# 08_SAMA7G54-DDR3.net
KiCad netlist of a schematic drawn in Altium Designer
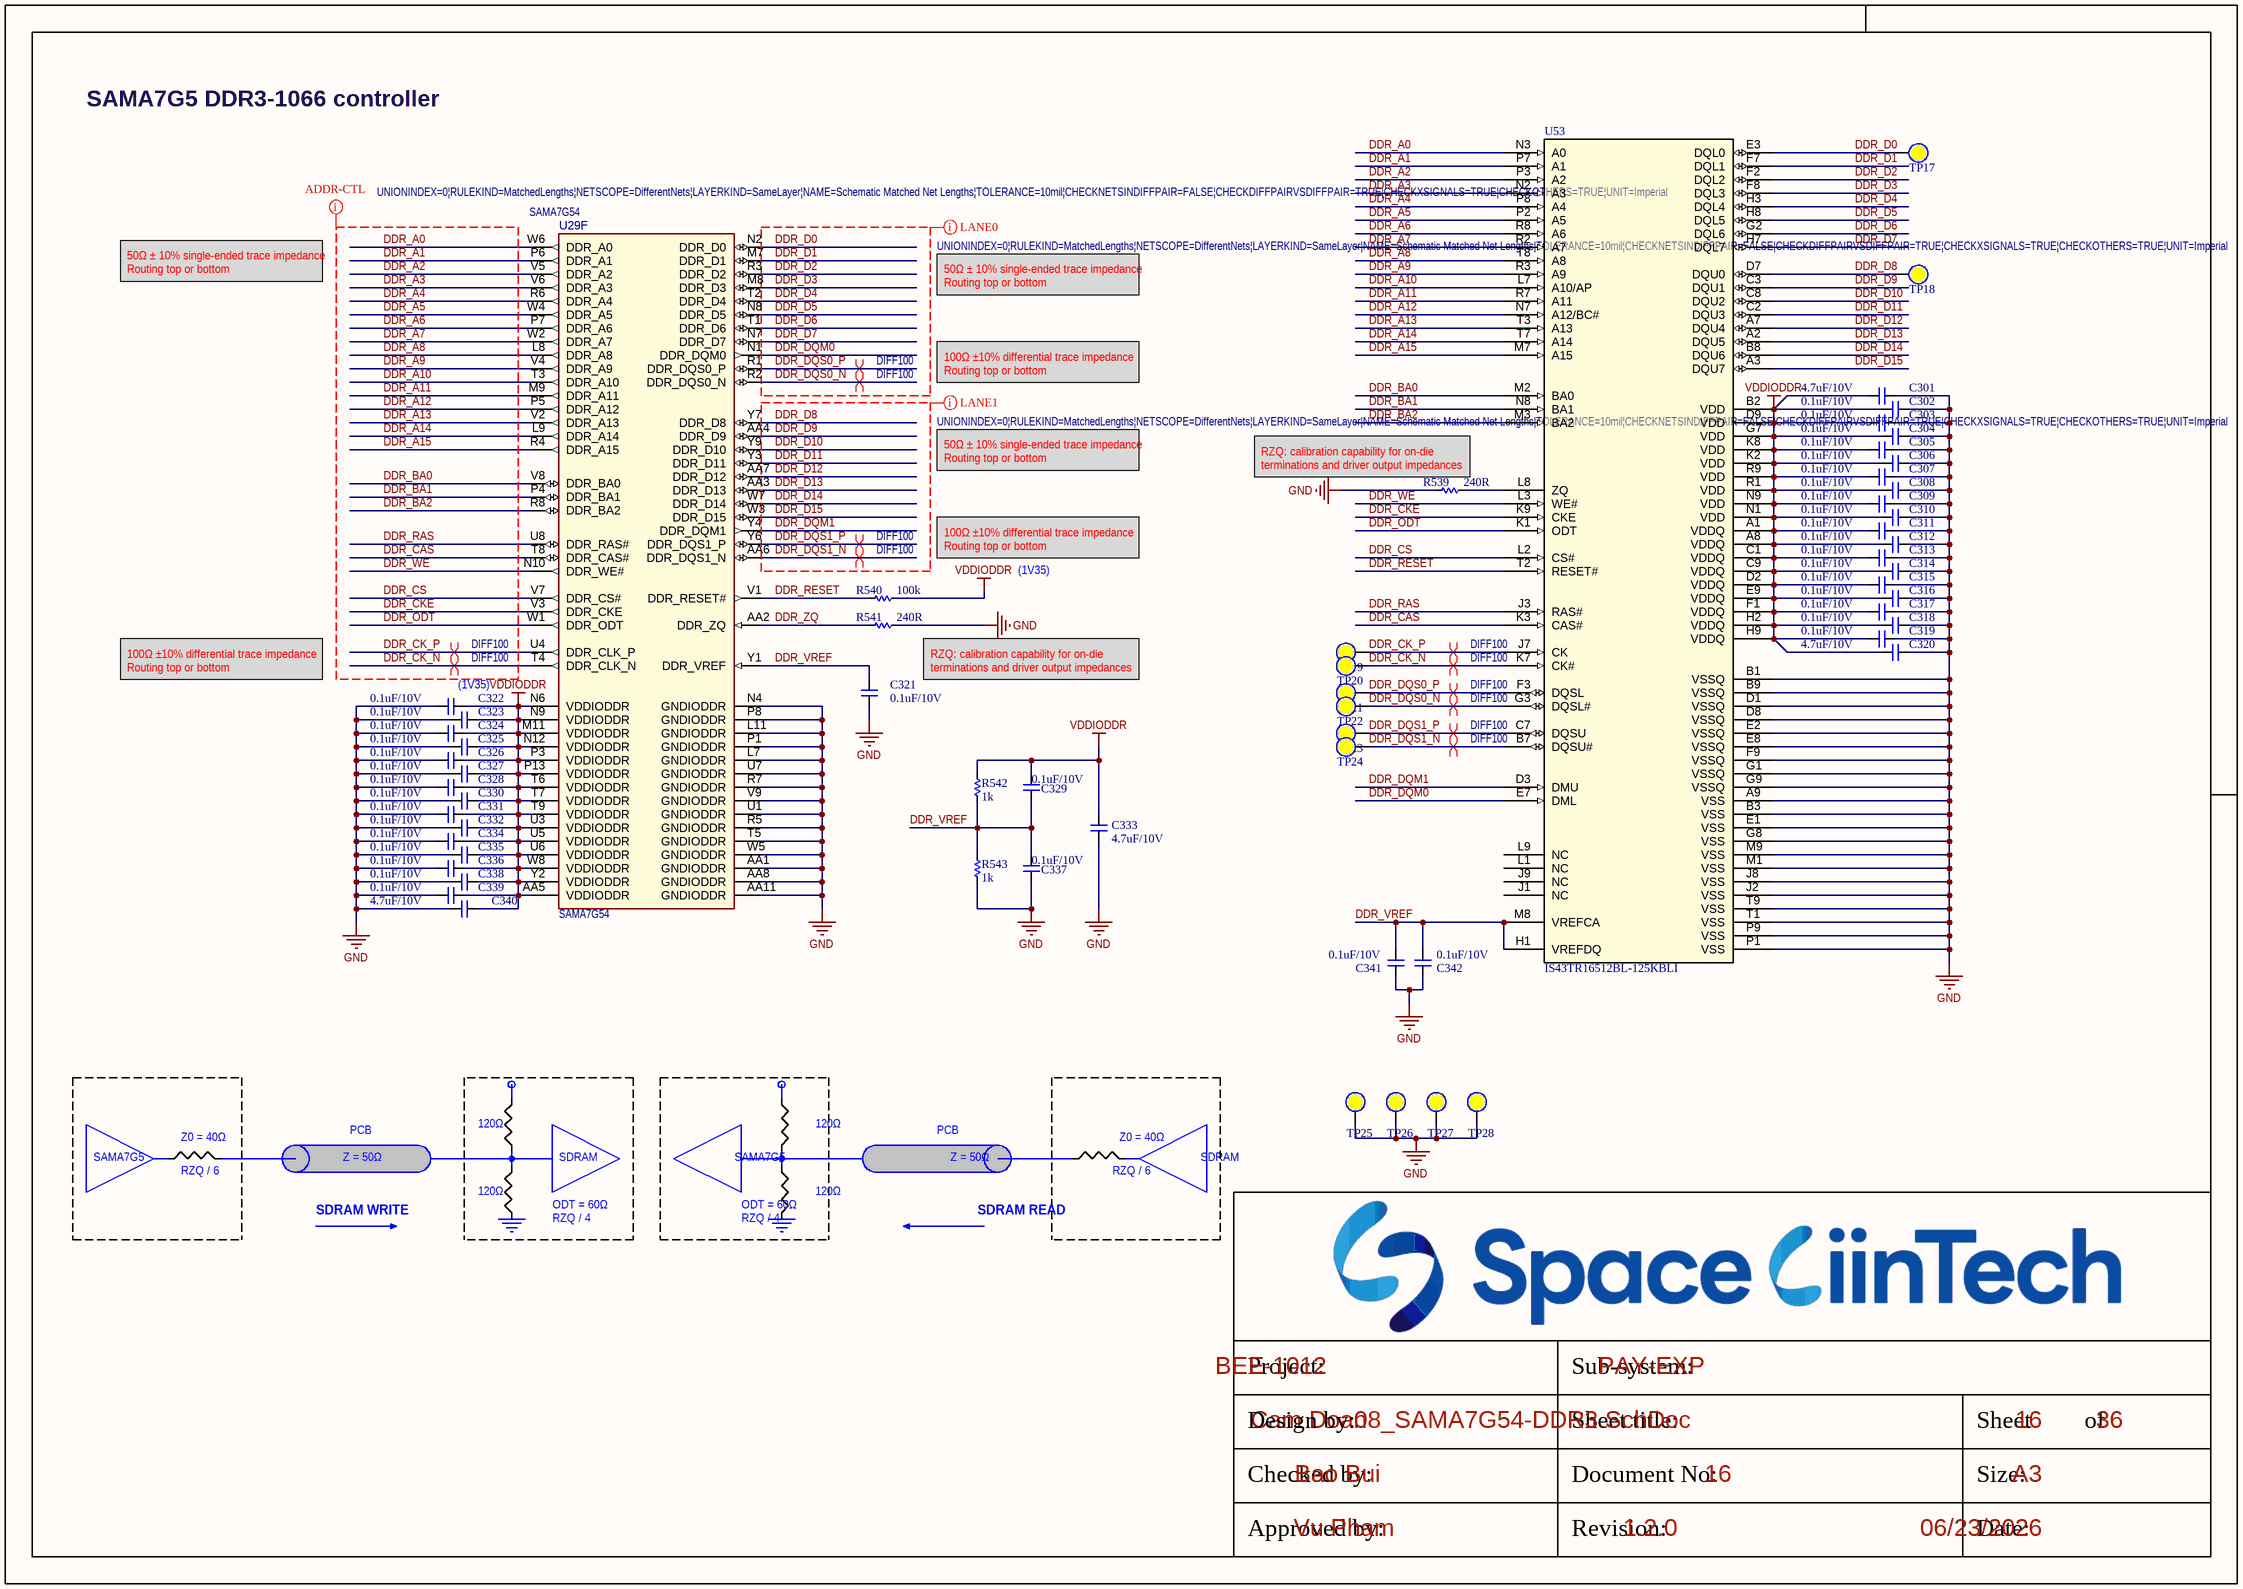
[diagram p0: 08_SAMA7G54-DDR3.SchDoc]

(export (version "E")
  (design (tool "Eeschema 10.0.6"))
  (components
    (comp (ref "C301")
      (value "4.7uF/10V")
      (footprint "CAP_C_1005X50_L")
      (description "CAP")
      (libsource (lib "LABLIB") (part "_CAP_C_2"))
    )
    (comp (ref "C302")
      (value "0.1uF/10V")
      (footprint "CAP_C_0603x30")
      (description "CAP")
      (libsource (lib "LABLIB") (part "_CAP_C_2"))
    )
    (comp (ref "C303")
      (value "0.1uF/10V")
      (footprint "CAP_C_0603x30")
      (description "CAP")
      (libsource (lib "LABLIB") (part "_CAP_C_2"))
    )
    (comp (ref "C304")
      (value "0.1uF/10V")
      (footprint "CAP_C_0603x30")
      (description "CAP")
      (libsource (lib "LABLIB") (part "_CAP_C_2"))
    )
    (comp (ref "C305")
      (value "0.1uF/10V")
      (footprint "CAP_C_0603x30")
      (description "CAP")
      (libsource (lib "LABLIB") (part "_CAP_C_2"))
    )
    (comp (ref "C306")
      (value "0.1uF/10V")
      (footprint "CAP_C_0603x30")
      (description "CAP")
      (libsource (lib "LABLIB") (part "_CAP_C_2"))
    )
    (comp (ref "C307")
      (value "0.1uF/10V")
      (footprint "CAP_C_0603x30")
      (description "CAP")
      (libsource (lib "LABLIB") (part "_CAP_C_2"))
    )
    (comp (ref "C308")
      (value "0.1uF/10V")
      (footprint "CAP_C_0603x30")
      (description "CAP")
      (libsource (lib "LABLIB") (part "_CAP_C_2"))
    )
    (comp (ref "C309")
      (value "0.1uF/10V")
      (footprint "CAP_C_0603x30")
      (description "CAP")
      (libsource (lib "LABLIB") (part "_CAP_C_2"))
    )
    (comp (ref "C310")
      (value "0.1uF/10V")
      (footprint "CAP_C_0603x30")
      (description "CAP")
      (libsource (lib "LABLIB") (part "_CAP_C_2"))
    )
    (comp (ref "C311")
      (value "0.1uF/10V")
      (footprint "CAP_C_0603x30")
      (description "CAP")
      (libsource (lib "LABLIB") (part "_CAP_C_2"))
    )
    (comp (ref "C312")
      (value "0.1uF/10V")
      (footprint "CAP_C_0603x30")
      (description "CAP")
      (libsource (lib "LABLIB") (part "_CAP_C_2"))
    )
    (comp (ref "C313")
      (value "0.1uF/10V")
      (footprint "CAP_C_0603x30")
      (description "CAP")
      (libsource (lib "LABLIB") (part "_CAP_C_2"))
    )
    (comp (ref "C314")
      (value "0.1uF/10V")
      (footprint "CAP_C_0603x30")
      (description "CAP")
      (libsource (lib "LABLIB") (part "_CAP_C_2"))
    )
    (comp (ref "C315")
      (value "0.1uF/10V")
      (footprint "CAP_C_0603x30")
      (description "CAP")
      (libsource (lib "LABLIB") (part "_CAP_C_2"))
    )
    (comp (ref "C316")
      (value "0.1uF/10V")
      (footprint "CAP_C_0603x30")
      (description "CAP")
      (libsource (lib "LABLIB") (part "_CAP_C_2"))
    )
    (comp (ref "C317")
      (value "0.1uF/10V")
      (footprint "CAP_C_0603x30")
      (description "CAP")
      (libsource (lib "LABLIB") (part "_CAP_C_2"))
    )
    (comp (ref "C318")
      (value "0.1uF/10V")
      (footprint "CAP_C_0603x30")
      (description "CAP")
      (libsource (lib "LABLIB") (part "_CAP_C_2"))
    )
    (comp (ref "C319")
      (value "0.1uF/10V")
      (footprint "CAP_C_0603x30")
      (description "CAP")
      (libsource (lib "LABLIB") (part "_CAP_C_2"))
    )
    (comp (ref "C320")
      (value "4.7uF/10V")
      (footprint "CAP_C_1005X50_L")
      (description "CAP")
      (libsource (lib "LABLIB") (part "_CAP_C_2"))
    )
    (comp (ref "C321")
      (value "0.1uF/10V")
      (footprint "CAP_C_0603x30")
      (description "CAP")
      (libsource (lib "LABLIB") (part "_CAP_C_2"))
    )
    (comp (ref "C322")
      (value "0.1uF/10V")
      (footprint "CAP_C_0603x30")
      (description "CAP")
      (libsource (lib "LABLIB") (part "_CAP_C_2"))
    )
    (comp (ref "C323")
      (value "0.1uF/10V")
      (footprint "CAP_C_0603x30")
      (description "CAP")
      (libsource (lib "LABLIB") (part "_CAP_C_2"))
    )
    (comp (ref "C324")
      (value "0.1uF/10V")
      (footprint "CAP_C_0603x30")
      (description "CAP")
      (libsource (lib "LABLIB") (part "_CAP_C_2"))
    )
    (comp (ref "C325")
      (value "0.1uF/10V")
      (footprint "CAP_C_0603x30")
      (description "CAP")
      (libsource (lib "LABLIB") (part "_CAP_C_2"))
    )
    (comp (ref "C326")
      (value "0.1uF/10V")
      (footprint "CAP_C_0603x30")
      (description "CAP")
      (libsource (lib "LABLIB") (part "_CAP_C_2"))
    )
    (comp (ref "C327")
      (value "0.1uF/10V")
      (footprint "CAP_C_0603x30")
      (description "CAP")
      (libsource (lib "LABLIB") (part "_CAP_C_2"))
    )
    (comp (ref "C328")
      (value "0.1uF/10V")
      (footprint "CAP_C_0603x30")
      (description "CAP")
      (libsource (lib "LABLIB") (part "_CAP_C_2"))
    )
    (comp (ref "C329")
      (value "0.1uF/10V")
      (footprint "CAP_C_0603x30")
      (description "CAP")
      (libsource (lib "LABLIB") (part "_CAP_C_2"))
    )
    (comp (ref "C330")
      (value "0.1uF/10V")
      (footprint "CAP_C_0603x30")
      (description "CAP")
      (libsource (lib "LABLIB") (part "_CAP_C_2"))
    )
    (comp (ref "C331")
      (value "0.1uF/10V")
      (footprint "CAP_C_0603x30")
      (description "CAP")
      (libsource (lib "LABLIB") (part "_CAP_C_2"))
    )
    (comp (ref "C332")
      (value "0.1uF/10V")
      (footprint "CAP_C_0603x30")
      (description "CAP")
      (libsource (lib "LABLIB") (part "_CAP_C_2"))
    )
    (comp (ref "C333")
      (value "4.7uF/10V")
      (footprint "CAP_C_1005X50_L")
      (description "CAP")
      (libsource (lib "LABLIB") (part "_CAP_C_2"))
    )
    (comp (ref "C334")
      (value "0.1uF/10V")
      (footprint "CAP_C_0603x30")
      (description "CAP")
      (libsource (lib "LABLIB") (part "_CAP_C_2"))
    )
    (comp (ref "C335")
      (value "0.1uF/10V")
      (footprint "CAP_C_0603x30")
      (description "CAP")
      (libsource (lib "LABLIB") (part "_CAP_C_2"))
    )
    (comp (ref "C336")
      (value "0.1uF/10V")
      (footprint "CAP_C_0603x30")
      (description "CAP")
      (libsource (lib "LABLIB") (part "_CAP_C_2"))
    )
    (comp (ref "C337")
      (value "0.1uF/10V")
      (footprint "CAP_C_0603x30")
      (description "CAP")
      (libsource (lib "LABLIB") (part "_CAP_C_2"))
    )
    (comp (ref "C338")
      (value "0.1uF/10V")
      (footprint "CAP_C_0603x30")
      (description "CAP")
      (libsource (lib "LABLIB") (part "_CAP_C_2"))
    )
    (comp (ref "C339")
      (value "0.1uF/10V")
      (footprint "CAP_C_0603x30")
      (description "CAP")
      (libsource (lib "LABLIB") (part "_CAP_C_2"))
    )
    (comp (ref "C340")
      (value "4.7uF/10V")
      (footprint "CAP_C_1005X50_L")
      (description "CAP")
      (libsource (lib "LABLIB") (part "_CAP_C_2"))
    )
    (comp (ref "C341")
      (value "0.1uF/10V")
      (footprint "CAP_C_0603x30")
      (description "CAP")
      (libsource (lib "LABLIB") (part "_CAP_C_2"))
    )
    (comp (ref "C342")
      (value "0.1uF/10V")
      (footprint "CAP_C_0603x30")
      (description "CAP")
      (libsource (lib "LABLIB") (part "_CAP_C_2"))
    )
    (comp (ref "R539")
      (value "240R")
      (footprint "RES_C_0603X30")
      (description "RES")
      (libsource (lib "LABLIB") (part "_RES_B_2"))
    )
    (comp (ref "R540")
      (value "100k")
      (footprint "RES_C_0603X30")
      (description "RES")
      (libsource (lib "LABLIB") (part "_RES_B_2"))
    )
    (comp (ref "R541")
      (value "240R")
      (footprint "RES_C_0603X30")
      (description "RES")
      (libsource (lib "LABLIB") (part "_RES_B_2"))
    )
    (comp (ref "R542")
      (value "1k")
      (footprint "RES_C_0603X30")
      (description "RES")
      (libsource (lib "LABLIB") (part "_RES_B_2"))
    )
    (comp (ref "R543")
      (value "1k")
      (footprint "RES_C_0603X30")
      (description "RES")
      (libsource (lib "LABLIB") (part "_RES_B_2"))
    )
    (comp (ref "TP17")
      (value "~")
      (footprint "Testpoint_80")
      (description "Test Point")
      (libsource (lib "") (part "Test Point_2"))
    )
    (comp (ref "TP18")
      (value "~")
      (footprint "Testpoint_80")
      (description "Test Point")
      (libsource (lib "") (part "Test Point_2"))
    )
    (comp (ref "TP19")
      (value "~")
      (footprint "Testpoint_80")
      (description "Test Point")
      (libsource (lib "") (part "Test Point_1"))
    )
    (comp (ref "TP20")
      (value "~")
      (footprint "Testpoint_80")
      (description "Test Point")
      (libsource (lib "") (part "Test Point_1"))
    )
    (comp (ref "TP21")
      (value "~")
      (footprint "Testpoint_80")
      (description "Test Point")
      (libsource (lib "") (part "Test Point_1"))
    )
    (comp (ref "TP22")
      (value "~")
      (footprint "Testpoint_80")
      (description "Test Point")
      (libsource (lib "") (part "Test Point_1"))
    )
    (comp (ref "TP23")
      (value "~")
      (footprint "Testpoint_80")
      (description "Test Point")
      (libsource (lib "") (part "Test Point_1"))
    )
    (comp (ref "TP24")
      (value "~")
      (footprint "Testpoint_80")
      (description "Test Point")
      (libsource (lib "") (part "Test Point_1"))
    )
    (comp (ref "TP25")
      (value "~")
      (footprint "Testpoint_80")
      (description "Test Point")
      (libsource (lib "LABLIB") (part "Test Point"))
    )
    (comp (ref "TP26")
      (value "~")
      (footprint "Testpoint_80")
      (description "Test Point")
      (libsource (lib "LABLIB") (part "Test Point"))
    )
    (comp (ref "TP27")
      (value "~")
      (footprint "Testpoint_80")
      (description "Test Point")
      (libsource (lib "LABLIB") (part "Test Point"))
    )
    (comp (ref "TP28")
      (value "~")
      (footprint "Testpoint_80")
      (description "Test Point")
      (libsource (lib "LABLIB") (part "Test Point"))
    )
    (comp (ref "U29")
      (value "SAMA7G54")
      (footprint "TFBGA-343_14x14 - 2.5mm")
      (description "SAMA7G54 MPU 1000MHz Cortex-A7 TFBGA-343")
      (fields (field (name "ALTIUM_VALUE") "SAMA7G54") (field (name "OWNER") "Ciprian Abramov"))
      (libsource (lib "LABLIB") (part "SAMA7G54"))
    )
    (comp (ref "U53")
      (value "IS43TR16512BL-125KBLI")
      (footprint "TWBGA96_ISI")
      (description "DDR3L")
      (fields (field (name "COPYRIGHT") "Copyright (C) 2025 Ultra Librarian. All rights reserved."))
      (libsource (lib "LABLIB") (part "IC_RAM_IS43TR16512BL-125KBLI"))
    )
  )
  (nets
    (net (code "1") (name "/DDR_A0") (class "Default")
      (node (ref "U29") (pin "W6") (pinfunction "DDR_A0_W6") (pintype "output"))
      (node (ref "U53") (pin "N3") (pinfunction "A0_N3") (pintype "input"))
    )
    (net (code "2") (name "/DDR_A1") (class "Default")
      (node (ref "U29") (pin "P6") (pinfunction "DDR_A1_P6") (pintype "output"))
      (node (ref "U53") (pin "P7") (pinfunction "A1_P7") (pintype "input"))
    )
    (net (code "3") (name "/DDR_A2") (class "Default")
      (node (ref "U29") (pin "V5") (pinfunction "DDR_A2_V5") (pintype "output"))
      (node (ref "U53") (pin "P3") (pinfunction "A2_P3") (pintype "input"))
    )
    (net (code "4") (name "/DDR_A3") (class "Default")
      (node (ref "U29") (pin "V6") (pinfunction "DDR_A3_V6") (pintype "output"))
      (node (ref "U53") (pin "N2") (pinfunction "A3_N2") (pintype "input"))
    )
    (net (code "5") (name "/DDR_A4") (class "Default")
      (node (ref "U29") (pin "R6") (pinfunction "DDR_A4_R6") (pintype "output"))
      (node (ref "U53") (pin "P8") (pinfunction "A4_P8") (pintype "input"))
    )
    (net (code "6") (name "/DDR_A5") (class "Default")
      (node (ref "U29") (pin "W4") (pinfunction "DDR_A5_W4") (pintype "output"))
      (node (ref "U53") (pin "P2") (pinfunction "A5_P2") (pintype "input"))
    )
    (net (code "7") (name "/DDR_A6") (class "Default")
      (node (ref "U29") (pin "P7") (pinfunction "DDR_A6_P7") (pintype "output"))
      (node (ref "U53") (pin "R8") (pinfunction "A6_R8") (pintype "input"))
    )
    (net (code "8") (name "/DDR_A7") (class "Default")
      (node (ref "U29") (pin "W2") (pinfunction "DDR_A7_W2") (pintype "output"))
      (node (ref "U53") (pin "R2") (pinfunction "A7_R2") (pintype "input"))
    )
    (net (code "9") (name "/DDR_A8") (class "Default")
      (node (ref "U29") (pin "L8") (pinfunction "DDR_A8_L8") (pintype "output"))
      (node (ref "U53") (pin "T8") (pinfunction "A8_T8") (pintype "input"))
    )
    (net (code "10") (name "/DDR_A9") (class "Default")
      (node (ref "U29") (pin "V4") (pinfunction "DDR_A9_V4") (pintype "output"))
      (node (ref "U53") (pin "R3") (pinfunction "A9_R3") (pintype "input"))
    )
    (net (code "11") (name "/DDR_A10") (class "Default")
      (node (ref "U29") (pin "T3") (pinfunction "DDR_A10_T3") (pintype "output"))
      (node (ref "U53") (pin "L7") (pinfunction "A10/AP_L7") (pintype "input"))
    )
    (net (code "12") (name "/DDR_A11") (class "Default")
      (node (ref "U29") (pin "M9") (pinfunction "DDR_A11_M9") (pintype "output"))
      (node (ref "U53") (pin "R7") (pinfunction "A11_R7") (pintype "input"))
    )
    (net (code "13") (name "/DDR_A12") (class "Default")
      (node (ref "U29") (pin "P5") (pinfunction "DDR_A12_P5") (pintype "output"))
      (node (ref "U53") (pin "N7") (pinfunction "A12/BC#_N7") (pintype "input"))
    )
    (net (code "14") (name "/DDR_A13") (class "Default")
      (node (ref "U29") (pin "V2") (pinfunction "DDR_A13_V2") (pintype "output"))
      (node (ref "U53") (pin "T3") (pinfunction "A13_T3") (pintype "input"))
    )
    (net (code "15") (name "/DDR_A14") (class "Default")
      (node (ref "U29") (pin "L9") (pinfunction "DDR_A14_L9") (pintype "output"))
      (node (ref "U53") (pin "T7") (pinfunction "A14_T7") (pintype "input"))
    )
    (net (code "16") (name "/DDR_A15") (class "Default")
      (node (ref "U29") (pin "R4") (pinfunction "DDR_A15_R4") (pintype "output"))
      (node (ref "U53") (pin "M7") (pinfunction "A15_M7") (pintype "input"))
    )
    (net (code "17") (name "/DDR_BA0") (class "Default")
      (node (ref "U29") (pin "V8") (pinfunction "DDR_BA0_V8") (pintype "bidirectional"))
      (node (ref "U53") (pin "M2") (pinfunction "BA0_M2") (pintype "input"))
    )
    (net (code "18") (name "/DDR_BA1") (class "Default")
      (node (ref "U29") (pin "P4") (pinfunction "DDR_BA1_P4") (pintype "bidirectional"))
      (node (ref "U53") (pin "N8") (pinfunction "BA1_N8") (pintype "input"))
    )
    (net (code "19") (name "/DDR_BA2") (class "Default")
      (node (ref "U29") (pin "R8") (pinfunction "DDR_BA2_R8") (pintype "bidirectional"))
      (node (ref "U53") (pin "M3") (pinfunction "BA2_M3") (pintype "input"))
    )
    (net (code "20") (name "/DDR_CAS") (class "Default")
      (node (ref "U29") (pin "T8") (pinfunction "DDR_CAS#_T8") (pintype "bidirectional"))
      (node (ref "U53") (pin "K3") (pinfunction "CAS#_K3") (pintype "input"))
    )
    (net (code "21") (name "/DDR_CKE") (class "Default")
      (node (ref "U29") (pin "V3") (pinfunction "DDR_CKE_V3") (pintype "output"))
      (node (ref "U53") (pin "K9") (pinfunction "CKE_K9") (pintype "input"))
    )
    (net (code "22") (name "/DDR_CK_N") (class "Default")
      (node (ref "TP20") (pin "1") (pinfunction "1_1") (pintype "passive"))
      (node (ref "U29") (pin "T4") (pinfunction "DDR_CLK_N_T4") (pintype "output"))
      (node (ref "U53") (pin "K7") (pinfunction "CK#_K7") (pintype "input"))
    )
    (net (code "23") (name "/DDR_CK_P") (class "Default")
      (node (ref "TP19") (pin "1") (pinfunction "1_1") (pintype "passive"))
      (node (ref "U29") (pin "U4") (pinfunction "DDR_CLK_P_U4") (pintype "output"))
      (node (ref "U53") (pin "J7") (pinfunction "CK_J7") (pintype "input"))
    )
    (net (code "24") (name "/DDR_CS") (class "Default")
      (node (ref "U29") (pin "V7") (pinfunction "DDR_CS#_V7") (pintype "output"))
      (node (ref "U53") (pin "L2") (pinfunction "CS#_L2") (pintype "input"))
    )
    (net (code "25") (name "/DDR_D0") (class "Default")
      (node (ref "TP17") (pin "1") (pinfunction "1_1") (pintype "passive"))
      (node (ref "U29") (pin "N2") (pinfunction "DDR_D0_N2") (pintype "bidirectional"))
      (node (ref "U53") (pin "E3") (pinfunction "DQL0_E3") (pintype "bidirectional"))
    )
    (net (code "26") (name "/DDR_D1") (class "Default")
      (node (ref "U29") (pin "M7") (pinfunction "DDR_D1_M7") (pintype "bidirectional"))
      (node (ref "U53") (pin "F7") (pinfunction "DQL1_F7") (pintype "bidirectional"))
    )
    (net (code "27") (name "/DDR_D2") (class "Default")
      (node (ref "U29") (pin "R3") (pinfunction "DDR_D2_R3") (pintype "bidirectional"))
      (node (ref "U53") (pin "F2") (pinfunction "DQL2_F2") (pintype "bidirectional"))
    )
    (net (code "28") (name "/DDR_D3") (class "Default")
      (node (ref "U29") (pin "M8") (pinfunction "DDR_D3_M8") (pintype "bidirectional"))
      (node (ref "U53") (pin "F8") (pinfunction "DQL3_F8") (pintype "bidirectional"))
    )
    (net (code "29") (name "/DDR_D4") (class "Default")
      (node (ref "U29") (pin "T2") (pinfunction "DDR_D4_T2") (pintype "bidirectional"))
      (node (ref "U53") (pin "H3") (pinfunction "DQL4_H3") (pintype "bidirectional"))
    )
    (net (code "30") (name "/DDR_D5") (class "Default")
      (node (ref "U29") (pin "N8") (pinfunction "DDR_D5_N8") (pintype "bidirectional"))
      (node (ref "U53") (pin "H8") (pinfunction "DQL5_H8") (pintype "bidirectional"))
    )
    (net (code "31") (name "/DDR_D6") (class "Default")
      (node (ref "U29") (pin "T1") (pinfunction "DDR_D6_T1") (pintype "bidirectional"))
      (node (ref "U53") (pin "G2") (pinfunction "DQL6_G2") (pintype "bidirectional"))
    )
    (net (code "32") (name "/DDR_D7") (class "Default")
      (node (ref "U29") (pin "N7") (pinfunction "DDR_D7_N7") (pintype "bidirectional"))
      (node (ref "U53") (pin "H7") (pinfunction "DQL7_H7") (pintype "bidirectional"))
    )
    (net (code "33") (name "/DDR_D8") (class "Default")
      (node (ref "TP18") (pin "1") (pinfunction "1_1") (pintype "passive"))
      (node (ref "U29") (pin "Y7") (pinfunction "DDR_D8_Y7") (pintype "bidirectional"))
      (node (ref "U53") (pin "D7") (pinfunction "DQU0_D7") (pintype "bidirectional"))
    )
    (net (code "34") (name "/DDR_D9") (class "Default")
      (node (ref "U29") (pin "AA4") (pinfunction "DDR_D9_AA4") (pintype "bidirectional"))
      (node (ref "U53") (pin "C3") (pinfunction "DQU1_C3") (pintype "bidirectional"))
    )
    (net (code "35") (name "/DDR_D10") (class "Default")
      (node (ref "U29") (pin "Y9") (pinfunction "DDR_D10_Y9") (pintype "bidirectional"))
      (node (ref "U53") (pin "C8") (pinfunction "DQU2_C8") (pintype "bidirectional"))
    )
    (net (code "36") (name "/DDR_D11") (class "Default")
      (node (ref "U29") (pin "Y3") (pinfunction "DDR_D11_Y3") (pintype "bidirectional"))
      (node (ref "U53") (pin "C2") (pinfunction "DQU3_C2") (pintype "bidirectional"))
    )
    (net (code "37") (name "/DDR_D12") (class "Default")
      (node (ref "U29") (pin "AA7") (pinfunction "DDR_D12_AA7") (pintype "bidirectional"))
      (node (ref "U53") (pin "A7") (pinfunction "DQU4_A7") (pintype "bidirectional"))
    )
    (net (code "38") (name "/DDR_D13") (class "Default")
      (node (ref "U29") (pin "AA3") (pinfunction "DDR_D13_AA3") (pintype "bidirectional"))
      (node (ref "U53") (pin "A2") (pinfunction "DQU5_A2") (pintype "bidirectional"))
    )
    (net (code "39") (name "/DDR_D14") (class "Default")
      (node (ref "U29") (pin "W7") (pinfunction "DDR_D14_W7") (pintype "bidirectional"))
      (node (ref "U53") (pin "B8") (pinfunction "DQU6_B8") (pintype "bidirectional"))
    )
    (net (code "40") (name "/DDR_D15") (class "Default")
      (node (ref "U29") (pin "W3") (pinfunction "DDR_D15_W3") (pintype "bidirectional"))
      (node (ref "U53") (pin "A3") (pinfunction "DQU7_A3") (pintype "bidirectional"))
    )
    (net (code "41") (name "/DDR_DQM0") (class "Default")
      (node (ref "U29") (pin "N1") (pinfunction "DDR_DQM0_N1") (pintype "output"))
      (node (ref "U53") (pin "E7") (pinfunction "DML_E7") (pintype "input"))
    )
    (net (code "42") (name "/DDR_DQM1") (class "Default")
      (node (ref "U29") (pin "Y4") (pinfunction "DDR_DQM1_Y4") (pintype "output"))
      (node (ref "U53") (pin "D3") (pinfunction "DMU_D3") (pintype "input"))
    )
    (net (code "43") (name "/DDR_DQS0_N") (class "Default")
      (node (ref "TP22") (pin "1") (pinfunction "1_1") (pintype "passive"))
      (node (ref "U29") (pin "R2") (pinfunction "DDR_DQS0_N_R2") (pintype "bidirectional"))
      (node (ref "U53") (pin "G3") (pinfunction "DQSL#_G3") (pintype "bidirectional"))
    )
    (net (code "44") (name "/DDR_DQS0_P") (class "Default")
      (node (ref "TP21") (pin "1") (pinfunction "1_1") (pintype "passive"))
      (node (ref "U29") (pin "R1") (pinfunction "DDR_DQS0_P_R1") (pintype "bidirectional"))
      (node (ref "U53") (pin "F3") (pinfunction "DQSL_F3") (pintype "bidirectional"))
    )
    (net (code "45") (name "/DDR_DQS1_N") (class "Default")
      (node (ref "TP24") (pin "1") (pinfunction "1_1") (pintype "passive"))
      (node (ref "U29") (pin "AA6") (pinfunction "DDR_DQS1_N_AA6") (pintype "bidirectional"))
      (node (ref "U53") (pin "B7") (pinfunction "DQSU#_B7") (pintype "bidirectional"))
    )
    (net (code "46") (name "/DDR_DQS1_P") (class "Default")
      (node (ref "TP23") (pin "1") (pinfunction "1_1") (pintype "passive"))
      (node (ref "U29") (pin "Y6") (pinfunction "DDR_DQS1_P_Y6") (pintype "bidirectional"))
      (node (ref "U53") (pin "C7") (pinfunction "DQSU_C7") (pintype "bidirectional"))
    )
    (net (code "47") (name "/DDR_ODT") (class "Default")
      (node (ref "U29") (pin "W1") (pinfunction "DDR_ODT_W1") (pintype "output"))
      (node (ref "U53") (pin "K1") (pinfunction "ODT_K1") (pintype "input"))
    )
    (net (code "48") (name "/DDR_RAS") (class "Default")
      (node (ref "U29") (pin "U8") (pinfunction "DDR_RAS#_U8") (pintype "bidirectional"))
      (node (ref "U53") (pin "J3") (pinfunction "RAS#_J3") (pintype "input"))
    )
    (net (code "49") (name "/DDR_RESET") (class "Default")
      (node (ref "R540") (pin "2") (pinfunction "2_2") (pintype "passive"))
      (node (ref "U29") (pin "V1") (pinfunction "DDR_RESET#_V1") (pintype "output"))
      (node (ref "U53") (pin "T2") (pinfunction "RESET#_T2") (pintype "input"))
    )
    (net (code "50") (name "/DDR_VREF") (class "Default")
      (node (ref "C321") (pin "1") (pinfunction "1_1") (pintype "passive"))
      (node (ref "C329") (pin "2") (pinfunction "2_2") (pintype "passive"))
      (node (ref "C337") (pin "1") (pinfunction "1_1") (pintype "passive"))
      (node (ref "C341") (pin "1") (pinfunction "1_1") (pintype "passive"))
      (node (ref "C342") (pin "1") (pinfunction "1_1") (pintype "passive"))
      (node (ref "R542") (pin "2") (pinfunction "2_2") (pintype "passive"))
      (node (ref "R543") (pin "1") (pinfunction "1_1") (pintype "passive"))
      (node (ref "U29") (pin "Y1") (pinfunction "DDR_VREF_Y1") (pintype "input"))
      (node (ref "U53") (pin "H1") (pinfunction "VREFDQ_H1") (pintype "power_in"))
      (node (ref "U53") (pin "M8") (pinfunction "VREFCA_M8") (pintype "power_in"))
    )
    (net (code "51") (name "/DDR_WE") (class "Default")
      (node (ref "U29") (pin "N10") (pinfunction "DDR_WE#_N10") (pintype "output"))
      (node (ref "U53") (pin "L3") (pinfunction "WE#_L3") (pintype "input"))
    )
    (net (code "52") (name "/DDR_ZQ") (class "Default")
      (node (ref "R541") (pin "2") (pinfunction "2_2") (pintype "passive"))
      (node (ref "U29") (pin "AA2") (pinfunction "DDR_ZQ_AA2") (pintype "input"))
    )
    (net (code "53") (name "GND") (class "Default")
      (node (ref "C301") (pin "1") (pinfunction "1_1") (pintype "passive"))
      (node (ref "C302") (pin "1") (pinfunction "1_1") (pintype "passive"))
      (node (ref "C303") (pin "1") (pinfunction "1_1") (pintype "passive"))
      (node (ref "C304") (pin "1") (pinfunction "1_1") (pintype "passive"))
      (node (ref "C305") (pin "1") (pinfunction "1_1") (pintype "passive"))
      (node (ref "C306") (pin "1") (pinfunction "1_1") (pintype "passive"))
      (node (ref "C307") (pin "1") (pinfunction "1_1") (pintype "passive"))
      (node (ref "C308") (pin "1") (pinfunction "1_1") (pintype "passive"))
      (node (ref "C309") (pin "1") (pinfunction "1_1") (pintype "passive"))
      (node (ref "C310") (pin "1") (pinfunction "1_1") (pintype "passive"))
      (node (ref "C311") (pin "1") (pinfunction "1_1") (pintype "passive"))
      (node (ref "C312") (pin "1") (pinfunction "1_1") (pintype "passive"))
      (node (ref "C313") (pin "1") (pinfunction "1_1") (pintype "passive"))
      (node (ref "C314") (pin "1") (pinfunction "1_1") (pintype "passive"))
      (node (ref "C315") (pin "1") (pinfunction "1_1") (pintype "passive"))
      (node (ref "C316") (pin "1") (pinfunction "1_1") (pintype "passive"))
      (node (ref "C317") (pin "1") (pinfunction "1_1") (pintype "passive"))
      (node (ref "C318") (pin "1") (pinfunction "1_1") (pintype "passive"))
      (node (ref "C319") (pin "1") (pinfunction "1_1") (pintype "passive"))
      (node (ref "C320") (pin "1") (pinfunction "1_1") (pintype "passive"))
      (node (ref "C321") (pin "2") (pinfunction "2_2") (pintype "passive"))
      (node (ref "C322") (pin "2") (pinfunction "2_2") (pintype "passive"))
      (node (ref "C323") (pin "2") (pinfunction "2_2") (pintype "passive"))
      (node (ref "C324") (pin "2") (pinfunction "2_2") (pintype "passive"))
      (node (ref "C325") (pin "2") (pinfunction "2_2") (pintype "passive"))
      (node (ref "C326") (pin "2") (pinfunction "2_2") (pintype "passive"))
      (node (ref "C327") (pin "2") (pinfunction "2_2") (pintype "passive"))
      (node (ref "C328") (pin "2") (pinfunction "2_2") (pintype "passive"))
      (node (ref "C330") (pin "2") (pinfunction "2_2") (pintype "passive"))
      (node (ref "C331") (pin "2") (pinfunction "2_2") (pintype "passive"))
      (node (ref "C332") (pin "2") (pinfunction "2_2") (pintype "passive"))
      (node (ref "C333") (pin "2") (pinfunction "2_2") (pintype "passive"))
      (node (ref "C334") (pin "2") (pinfunction "2_2") (pintype "passive"))
      (node (ref "C335") (pin "2") (pinfunction "2_2") (pintype "passive"))
      (node (ref "C336") (pin "2") (pinfunction "2_2") (pintype "passive"))
      (node (ref "C337") (pin "2") (pinfunction "2_2") (pintype "passive"))
      (node (ref "C338") (pin "2") (pinfunction "2_2") (pintype "passive"))
      (node (ref "C339") (pin "2") (pinfunction "2_2") (pintype "passive"))
      (node (ref "C340") (pin "2") (pinfunction "2_2") (pintype "passive"))
      (node (ref "C341") (pin "2") (pinfunction "2_2") (pintype "passive"))
      (node (ref "C342") (pin "2") (pinfunction "2_2") (pintype "passive"))
      (node (ref "R539") (pin "2") (pinfunction "2_2") (pintype "passive"))
      (node (ref "R541") (pin "1") (pinfunction "1_1") (pintype "passive"))
      (node (ref "R543") (pin "2") (pinfunction "2_2") (pintype "passive"))
      (node (ref "TP25") (pin "1") (pinfunction "1_1") (pintype "passive"))
      (node (ref "TP26") (pin "1") (pinfunction "1_1") (pintype "passive"))
      (node (ref "TP27") (pin "1") (pinfunction "1_1") (pintype "passive"))
      (node (ref "TP28") (pin "1") (pinfunction "1_1") (pintype "passive"))
      (node (ref "U29") (pin "AA1") (pinfunction "GNDIODDR_AA1") (pintype "power_in"))
      (node (ref "U29") (pin "AA11") (pinfunction "GNDIODDR_AA11") (pintype "power_in"))
      (node (ref "U29") (pin "AA8") (pinfunction "GNDIODDR_AA8") (pintype "power_in"))
      (node (ref "U29") (pin "L11") (pinfunction "GNDIODDR_L11") (pintype "power_in"))
      (node (ref "U29") (pin "L7") (pinfunction "GNDIODDR_L7") (pintype "power_in"))
      (node (ref "U29") (pin "N4") (pinfunction "GNDIODDR_N4") (pintype "power_in"))
      (node (ref "U29") (pin "P1") (pinfunction "GNDIODDR_P1") (pintype "power_in"))
      (node (ref "U29") (pin "P8") (pinfunction "GNDIODDR_P8") (pintype "power_in"))
      (node (ref "U29") (pin "R5") (pinfunction "GNDIODDR_R5") (pintype "power_in"))
      (node (ref "U29") (pin "R7") (pinfunction "GNDIODDR_R7") (pintype "power_in"))
      (node (ref "U29") (pin "T5") (pinfunction "GNDIODDR_T5") (pintype "power_in"))
      (node (ref "U29") (pin "U1") (pinfunction "GNDIODDR_U1") (pintype "power_in"))
      (node (ref "U29") (pin "U7") (pinfunction "GNDIODDR_U7") (pintype "power_in"))
      (node (ref "U29") (pin "V9") (pinfunction "GNDIODDR_V9") (pintype "power_in"))
      (node (ref "U29") (pin "W5") (pinfunction "GNDIODDR_W5") (pintype "power_in"))
      (node (ref "U53") (pin "A9") (pinfunction "VSS_A9") (pintype "power_in"))
      (node (ref "U53") (pin "B1") (pinfunction "VSSQ_B1") (pintype "power_in"))
      (node (ref "U53") (pin "B3") (pinfunction "VSS_B3") (pintype "power_in"))
      (node (ref "U53") (pin "B9") (pinfunction "VSSQ_B9") (pintype "power_in"))
      (node (ref "U53") (pin "D1") (pinfunction "VSSQ_D1") (pintype "power_in"))
      (node (ref "U53") (pin "D8") (pinfunction "VSSQ_D8") (pintype "power_in"))
      (node (ref "U53") (pin "E1") (pinfunction "VSS_E1") (pintype "power_in"))
      (node (ref "U53") (pin "E2") (pinfunction "VSSQ_E2") (pintype "power_in"))
      (node (ref "U53") (pin "E8") (pinfunction "VSSQ_E8") (pintype "power_in"))
      (node (ref "U53") (pin "F9") (pinfunction "VSSQ_F9") (pintype "power_in"))
      (node (ref "U53") (pin "G1") (pinfunction "VSSQ_G1") (pintype "power_in"))
      (node (ref "U53") (pin "G8") (pinfunction "VSS_G8") (pintype "power_in"))
      (node (ref "U53") (pin "G9") (pinfunction "VSSQ_G9") (pintype "power_in"))
      (node (ref "U53") (pin "J2") (pinfunction "VSS_J2") (pintype "power_in"))
      (node (ref "U53") (pin "J8") (pinfunction "VSS_J8") (pintype "power_in"))
      (node (ref "U53") (pin "M1") (pinfunction "VSS_M1") (pintype "power_in"))
      (node (ref "U53") (pin "M9") (pinfunction "VSS_M9") (pintype "power_in"))
      (node (ref "U53") (pin "P1") (pinfunction "VSS_P1") (pintype "power_in"))
      (node (ref "U53") (pin "P9") (pinfunction "VSS_P9") (pintype "power_in"))
      (node (ref "U53") (pin "T1") (pinfunction "VSS_T1") (pintype "power_in"))
      (node (ref "U53") (pin "T9") (pinfunction "VSS_T9") (pintype "power_in"))
    )
    (net (code "54") (name "Net-(U53-ZQ)") (class "Default")
      (node (ref "R539") (pin "1") (pinfunction "1_1") (pintype "passive"))
      (node (ref "U53") (pin "L8") (pinfunction "ZQ_L8") (pintype "power_in"))
    )
    (net (code "55") (name "VDDIODDR") (class "Default")
      (node (ref "C301") (pin "2") (pinfunction "2_2") (pintype "passive"))
      (node (ref "C302") (pin "2") (pinfunction "2_2") (pintype "passive"))
      (node (ref "C303") (pin "2") (pinfunction "2_2") (pintype "passive"))
      (node (ref "C304") (pin "2") (pinfunction "2_2") (pintype "passive"))
      (node (ref "C305") (pin "2") (pinfunction "2_2") (pintype "passive"))
      (node (ref "C306") (pin "2") (pinfunction "2_2") (pintype "passive"))
      (node (ref "C307") (pin "2") (pinfunction "2_2") (pintype "passive"))
      (node (ref "C308") (pin "2") (pinfunction "2_2") (pintype "passive"))
      (node (ref "C309") (pin "2") (pinfunction "2_2") (pintype "passive"))
      (node (ref "C310") (pin "2") (pinfunction "2_2") (pintype "passive"))
      (node (ref "C311") (pin "2") (pinfunction "2_2") (pintype "passive"))
      (node (ref "C312") (pin "2") (pinfunction "2_2") (pintype "passive"))
      (node (ref "C313") (pin "2") (pinfunction "2_2") (pintype "passive"))
      (node (ref "C314") (pin "2") (pinfunction "2_2") (pintype "passive"))
      (node (ref "C315") (pin "2") (pinfunction "2_2") (pintype "passive"))
      (node (ref "C316") (pin "2") (pinfunction "2_2") (pintype "passive"))
      (node (ref "C317") (pin "2") (pinfunction "2_2") (pintype "passive"))
      (node (ref "C318") (pin "2") (pinfunction "2_2") (pintype "passive"))
      (node (ref "C319") (pin "2") (pinfunction "2_2") (pintype "passive"))
      (node (ref "C320") (pin "2") (pinfunction "2_2") (pintype "passive"))
      (node (ref "C322") (pin "1") (pinfunction "1_1") (pintype "passive"))
      (node (ref "C323") (pin "1") (pinfunction "1_1") (pintype "passive"))
      (node (ref "C324") (pin "1") (pinfunction "1_1") (pintype "passive"))
      (node (ref "C325") (pin "1") (pinfunction "1_1") (pintype "passive"))
      (node (ref "C326") (pin "1") (pinfunction "1_1") (pintype "passive"))
      (node (ref "C327") (pin "1") (pinfunction "1_1") (pintype "passive"))
      (node (ref "C328") (pin "1") (pinfunction "1_1") (pintype "passive"))
      (node (ref "C329") (pin "1") (pinfunction "1_1") (pintype "passive"))
      (node (ref "C330") (pin "1") (pinfunction "1_1") (pintype "passive"))
      (node (ref "C331") (pin "1") (pinfunction "1_1") (pintype "passive"))
      (node (ref "C332") (pin "1") (pinfunction "1_1") (pintype "passive"))
      (node (ref "C333") (pin "1") (pinfunction "1_1") (pintype "passive"))
      (node (ref "C334") (pin "1") (pinfunction "1_1") (pintype "passive"))
      (node (ref "C335") (pin "1") (pinfunction "1_1") (pintype "passive"))
      (node (ref "C336") (pin "1") (pinfunction "1_1") (pintype "passive"))
      (node (ref "C338") (pin "1") (pinfunction "1_1") (pintype "passive"))
      (node (ref "C339") (pin "1") (pinfunction "1_1") (pintype "passive"))
      (node (ref "C340") (pin "1") (pinfunction "1_1") (pintype "passive"))
      (node (ref "R540") (pin "1") (pinfunction "1_1") (pintype "passive"))
      (node (ref "R542") (pin "1") (pinfunction "1_1") (pintype "passive"))
      (node (ref "U29") (pin "AA5") (pinfunction "VDDIODDR_AA5") (pintype "power_in"))
      (node (ref "U29") (pin "M11") (pinfunction "VDDIODDR_M11") (pintype "power_in"))
      (node (ref "U29") (pin "N12") (pinfunction "VDDIODDR_N12") (pintype "power_in"))
      (node (ref "U29") (pin "N6") (pinfunction "VDDIODDR_N6") (pintype "power_in"))
      (node (ref "U29") (pin "N9") (pinfunction "VDDIODDR_N9") (pintype "power_in"))
      (node (ref "U29") (pin "P13") (pinfunction "VDDIODDR_P13") (pintype "power_in"))
      (node (ref "U29") (pin "P3") (pinfunction "VDDIODDR_P3") (pintype "power_in"))
      (node (ref "U29") (pin "T6") (pinfunction "VDDIODDR_T6") (pintype "power_in"))
      (node (ref "U29") (pin "T7") (pinfunction "VDDIODDR_T7") (pintype "power_in"))
      (node (ref "U29") (pin "T9") (pinfunction "VDDIODDR_T9") (pintype "power_in"))
      (node (ref "U29") (pin "U3") (pinfunction "VDDIODDR_U3") (pintype "power_in"))
      (node (ref "U29") (pin "U5") (pinfunction "VDDIODDR_U5") (pintype "power_in"))
      (node (ref "U29") (pin "U6") (pinfunction "VDDIODDR_U6") (pintype "power_in"))
      (node (ref "U29") (pin "W8") (pinfunction "VDDIODDR_W8") (pintype "power_in"))
      (node (ref "U29") (pin "Y2") (pinfunction "VDDIODDR_Y2") (pintype "power_in"))
      (node (ref "U53") (pin "A1") (pinfunction "VDDQ_A1") (pintype "power_in"))
      (node (ref "U53") (pin "A8") (pinfunction "VDDQ_A8") (pintype "power_in"))
      (node (ref "U53") (pin "B2") (pinfunction "VDD_B2") (pintype "power_in"))
      (node (ref "U53") (pin "C1") (pinfunction "VDDQ_C1") (pintype "power_in"))
      (node (ref "U53") (pin "C9") (pinfunction "VDDQ_C9") (pintype "power_in"))
      (node (ref "U53") (pin "D2") (pinfunction "VDDQ_D2") (pintype "power_in"))
      (node (ref "U53") (pin "D9") (pinfunction "VDD_D9") (pintype "power_in"))
      (node (ref "U53") (pin "E9") (pinfunction "VDDQ_E9") (pintype "power_in"))
      (node (ref "U53") (pin "F1") (pinfunction "VDDQ_F1") (pintype "power_in"))
      (node (ref "U53") (pin "G7") (pinfunction "VDD_G7") (pintype "power_in"))
      (node (ref "U53") (pin "H2") (pinfunction "VDDQ_H2") (pintype "power_in"))
      (node (ref "U53") (pin "H9") (pinfunction "VDDQ_H9") (pintype "power_in"))
      (node (ref "U53") (pin "K2") (pinfunction "VDD_K2") (pintype "power_in"))
      (node (ref "U53") (pin "K8") (pinfunction "VDD_K8") (pintype "power_in"))
      (node (ref "U53") (pin "N1") (pinfunction "VDD_N1") (pintype "power_in"))
      (node (ref "U53") (pin "N9") (pinfunction "VDD_N9") (pintype "power_in"))
      (node (ref "U53") (pin "R1") (pinfunction "VDD_R1") (pintype "power_in"))
      (node (ref "U53") (pin "R9") (pinfunction "VDD_R9") (pintype "power_in"))
    )
    (net (code "56") (name "unconnected-(U53-NC-PadJ1)") (class "Default")
      (node (ref "U53") (pin "J1") (pinfunction "NC_J1") (pintype "passive"))
    )
    (net (code "57") (name "unconnected-(U53-NC-PadJ9)") (class "Default")
      (node (ref "U53") (pin "J9") (pinfunction "NC_J9") (pintype "passive"))
    )
    (net (code "58") (name "unconnected-(U53-NC-PadL1)") (class "Default")
      (node (ref "U53") (pin "L1") (pinfunction "NC_L1") (pintype "passive"))
    )
    (net (code "59") (name "unconnected-(U53-NC-PadL9)") (class "Default")
      (node (ref "U53") (pin "L9") (pinfunction "NC_L9") (pintype "passive"))
    )
  )
)
